# 468332_001_Interface.net
KiCad netlist of a schematic drawn in Altium Designer
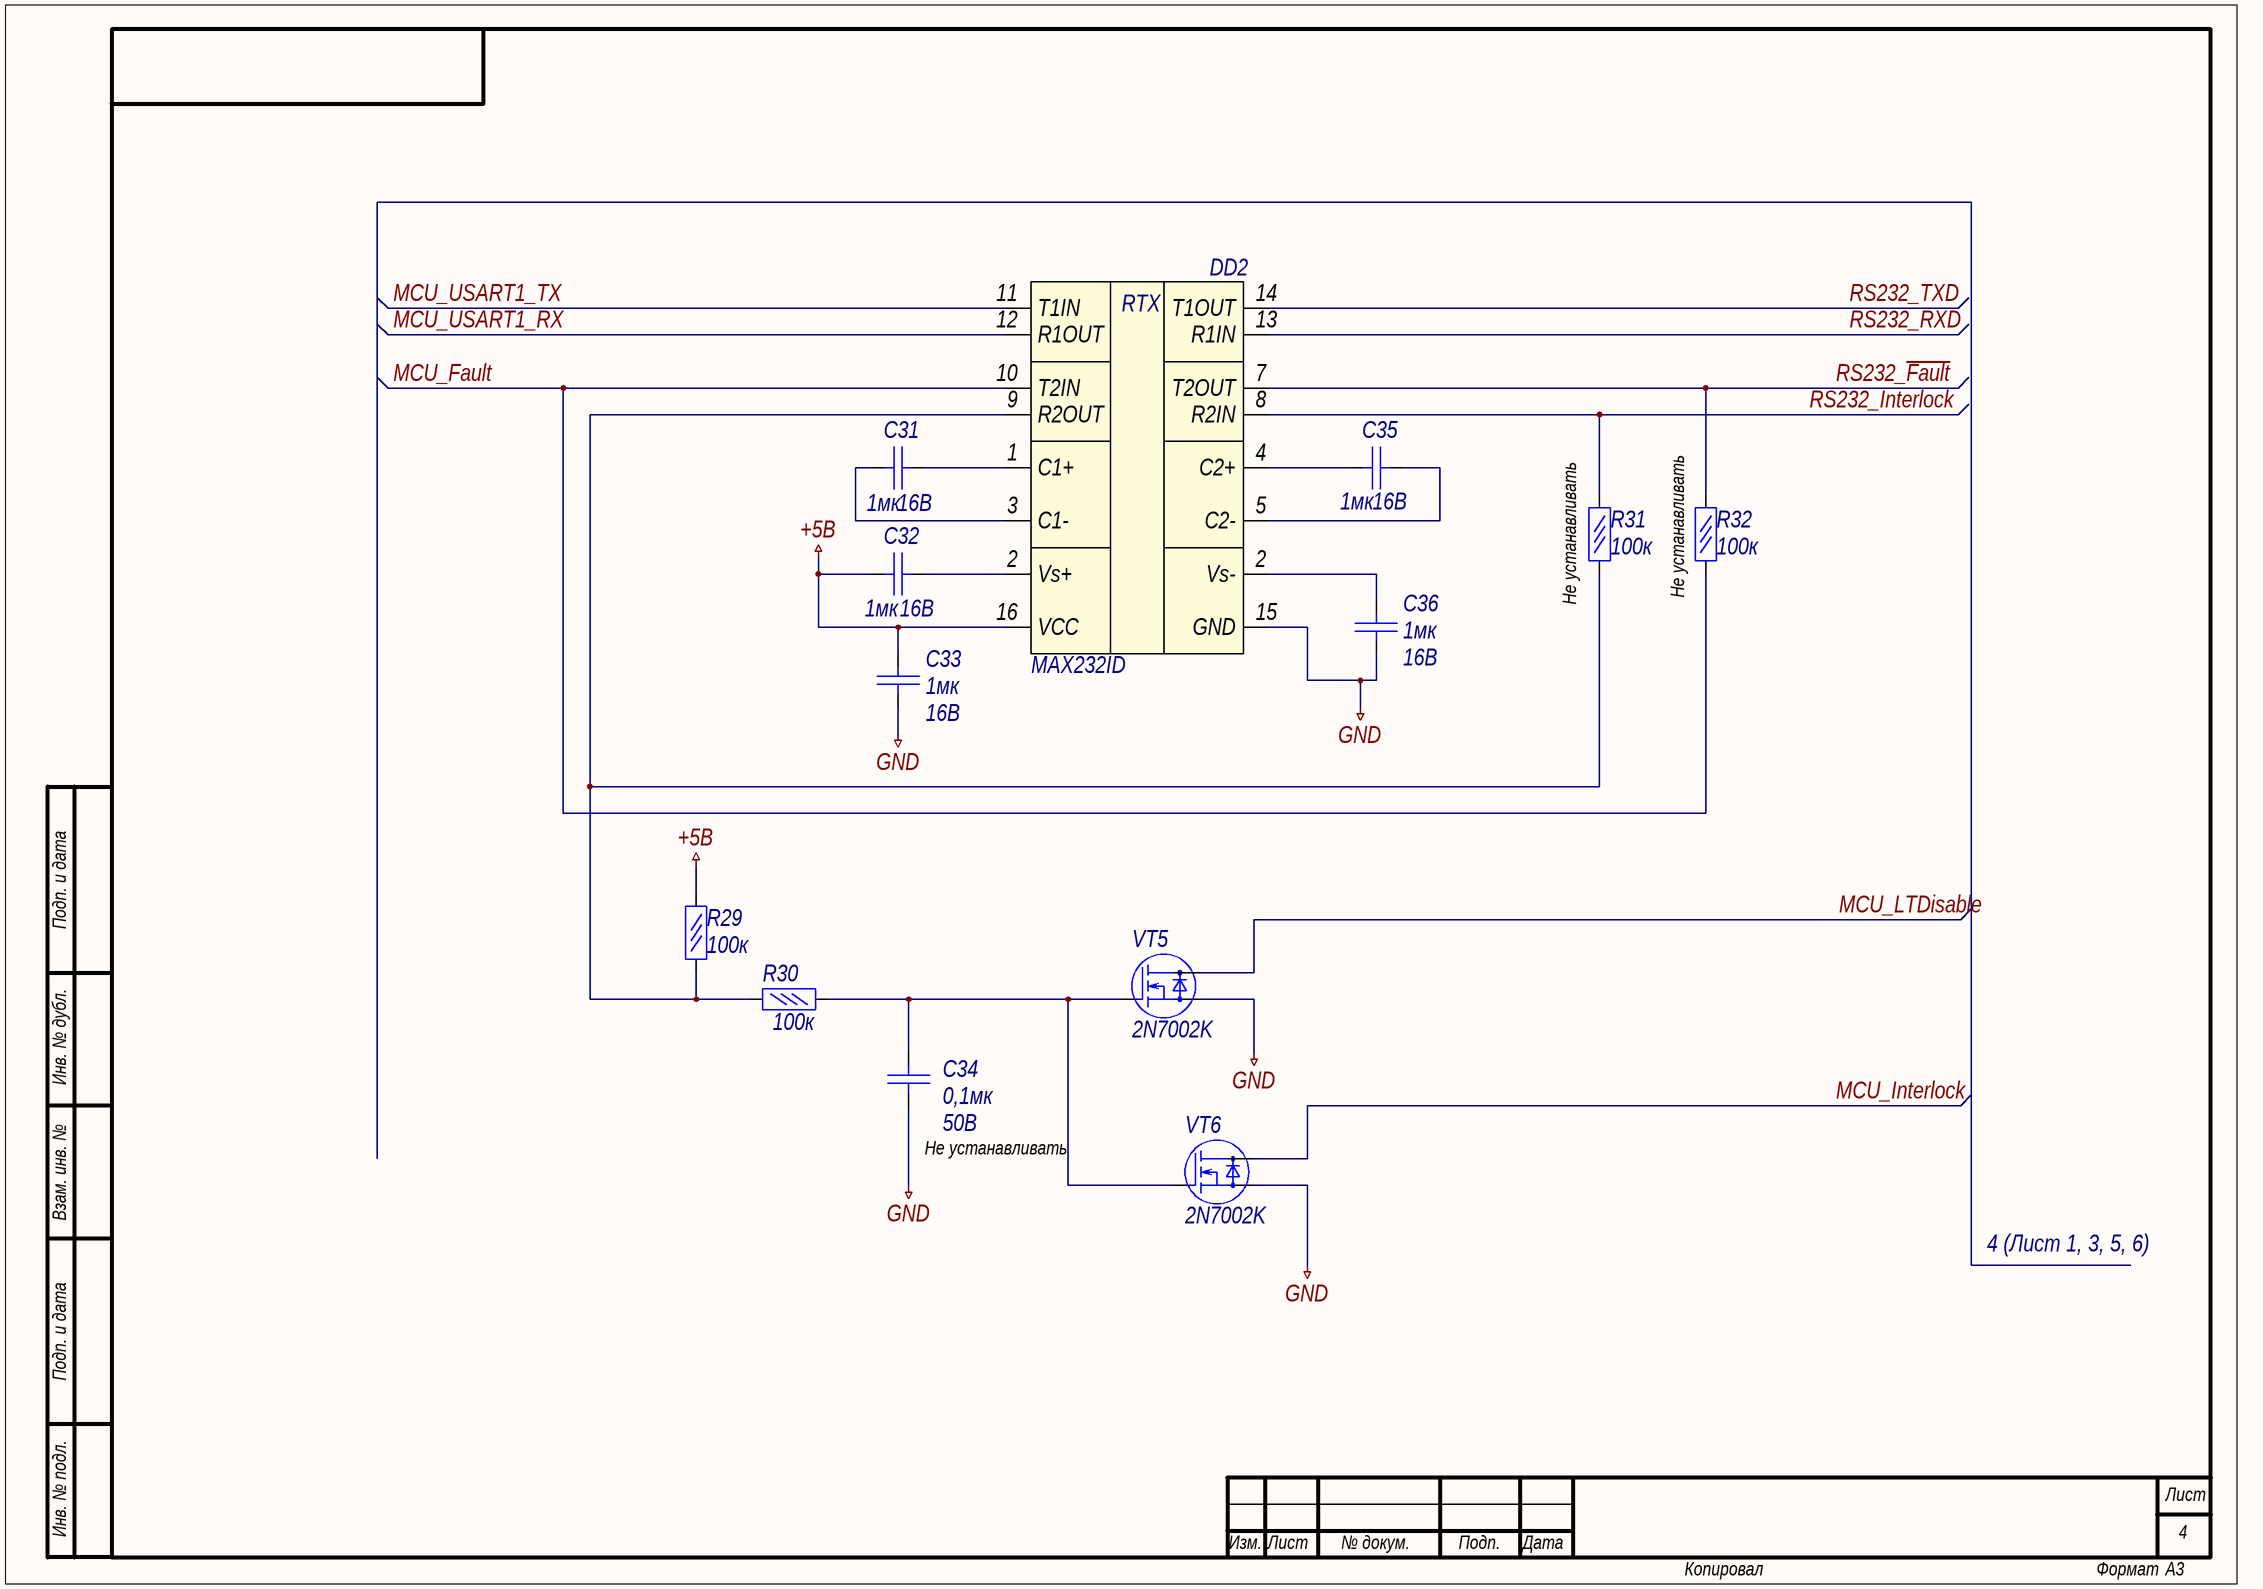
[diagram p0: РЕУН.468332.001_Interface.SchDoc]

(export (version "E")
  (design (tool "Eeschema 10.0.6"))
  (components
    (comp (ref "C31")
      (value "1мк")
      (footprint "C0805_AA")
      (description "Конденсатор кер.")
      (fields (field (name "VOLTAGE") "16В"))
      (libsource (lib "Library_Diana") (part "Конденсатор кер."))
    )
    (comp (ref "C32")
      (value "1мк")
      (footprint "C0805_AA")
      (description "Конденсатор кер.")
      (fields (field (name "VOLTAGE") "16В"))
      (libsource (lib "Library_Diana") (part "Конденсатор кер."))
    )
    (comp (ref "C33")
      (value "1мк")
      (footprint "C0805_AA")
      (description "Конденсатор кер.")
      (fields (field (name "VOLTAGE") "16В"))
      (libsource (lib "Library_Diana") (part "Конденсатор кер."))
    )
    (comp (ref "C34")
      (value "0,1мк")
      (footprint "C0805_AA")
      (description "Конденсатор кер.")
      (fields (field (name "VOLTAGE") "50В"))
      (libsource (lib "Library_Diana") (part "Конденсатор кер."))
    )
    (comp (ref "C35")
      (value "1мк")
      (footprint "C0805_AA")
      (description "Конденсатор кер.")
      (fields (field (name "VOLTAGE") "16В"))
      (libsource (lib "Library_Diana") (part "Конденсатор кер."))
    )
    (comp (ref "C36")
      (value "1мк")
      (footprint "C0805_AA")
      (description "Конденсатор кер.")
      (fields (field (name "VOLTAGE") "16В"))
      (libsource (lib "Library_Diana") (part "Конденсатор кер."))
    )
    (comp (ref "DD2")
      (value "MAX232ID")
      (description "Dual EIA-232 Drivers/Receivers")
      (libsource (lib "Library_Diana") (part "MAX232ID"))
    )
    (comp (ref "R29")
      (value "100к")
      (footprint "R1206")
      (description "Резистор 0,05Вт")
      (libsource (lib "Library_Diana") (part "Резистор  0,05Вт"))
    )
    (comp (ref "R30")
      (value "100к")
      (footprint "R1206")
      (description "Резистор 0,05Вт")
      (libsource (lib "") (part "Резистор  0,05Вт_1"))
    )
    (comp (ref "R31")
      (value "100к")
      (footprint "R1206")
      (description "Резистор 0,05Вт")
      (libsource (lib "Library_Diana") (part "Резистор  0,05Вт"))
    )
    (comp (ref "R32")
      (value "100к")
      (footprint "R1206")
      (description "Резистор 0,05Вт")
      (libsource (lib "Library_Diana") (part "Резистор  0,05Вт"))
    )
    (comp (ref "VT5")
      (value "2N7002K")
      (footprint "SOT:SOT23-3")
      (fields (field (name "NAME") "2N7002K"))
      (libsource (lib "Library_Diana") (part "mosfet-n"))
    )
    (comp (ref "VT6")
      (value "2N7002K")
      (footprint "SOT:SOT23-3")
      (fields (field (name "NAME") "2N7002K"))
      (libsource (lib "Library_Diana") (part "mosfet-n"))
    )
  )
  (nets
    (net (code "1") (name "+5В") (class "Default")
      (node (ref "C32") (pin "2") (pinfunction "2_2") (pintype "passive"))
      (node (ref "C33") (pin "1") (pinfunction "1_1") (pintype "passive"))
      (node (ref "DD2") (pin "16") (pinfunction "VCC_16") (pintype "passive"))
      (node (ref "R29") (pin "1") (pinfunction "1_1") (pintype "passive"))
    )
    (net (code "2") (name "/MCU_Fault") (class "Default")
      (node (ref "DD2") (pin "10") (pinfunction "T2IN_10") (pintype "passive"))
      (node (ref "R32") (pin "2") (pinfunction "2_2") (pintype "passive"))
    )
    (net (code "3") (name "/MCU_Interlock") (class "Default")
      (node (ref "VT6") (pin "3") (pinfunction "D_3") (pintype "passive"))
    )
    (net (code "4") (name "/MCU_LTDisable") (class "Default")
      (node (ref "VT5") (pin "3") (pinfunction "D_3") (pintype "passive"))
    )
    (net (code "5") (name "/MCU_USART1_RX") (class "Default")
      (node (ref "DD2") (pin "12") (pinfunction "R1OUT_12") (pintype "passive"))
    )
    (net (code "6") (name "/MCU_USART1_TX") (class "Default")
      (node (ref "DD2") (pin "11") (pinfunction "T1IN_11") (pintype "passive"))
    )
    (net (code "7") (name "/RS232_Interlock") (class "Default")
      (node (ref "DD2") (pin "8") (pinfunction "R2IN_8") (pintype "passive"))
      (node (ref "R31") (pin "1") (pinfunction "1_1") (pintype "passive"))
    )
    (net (code "8") (name "/RS232_RXD") (class "Default")
      (node (ref "DD2") (pin "13") (pinfunction "R1IN_13") (pintype "passive"))
    )
    (net (code "9") (name "/RS232_TXD") (class "Default")
      (node (ref "DD2") (pin "14") (pinfunction "T1OUT_14") (pintype "passive"))
    )
    (net (code "10") (name "/RS232_~{Fault}") (class "Default")
      (node (ref "DD2") (pin "7") (pinfunction "T2OUT_7") (pintype "passive"))
      (node (ref "R32") (pin "1") (pinfunction "1_1") (pintype "passive"))
    )
    (net (code "11") (name "GND") (class "Default")
      (node (ref "C33") (pin "2") (pinfunction "2_2") (pintype "passive"))
      (node (ref "C34") (pin "1") (pinfunction "1_1") (pintype "passive"))
      (node (ref "C36") (pin "2") (pinfunction "2_2") (pintype "passive"))
      (node (ref "DD2") (pin "15") (pinfunction "GND_15") (pintype "passive"))
      (node (ref "VT5") (pin "2") (pinfunction "S_2") (pintype "passive"))
      (node (ref "VT6") (pin "2") (pinfunction "S_2") (pintype "passive"))
    )
    (net (code "12") (name "Net-(DD2-C1+)") (class "Default")
      (node (ref "C31") (pin "1") (pinfunction "1_1") (pintype "passive"))
      (node (ref "DD2") (pin "1") (pinfunction "C1+_1") (pintype "passive"))
    )
    (net (code "13") (name "Net-(DD2-C1-)") (class "Default")
      (node (ref "C31") (pin "2") (pinfunction "2_2") (pintype "passive"))
      (node (ref "DD2") (pin "3") (pinfunction "C1-_3") (pintype "passive"))
    )
    (net (code "14") (name "Net-(DD2-C2+)") (class "Default")
      (node (ref "C35") (pin "2") (pinfunction "2_2") (pintype "passive"))
      (node (ref "DD2") (pin "4") (pinfunction "C2+_4") (pintype "passive"))
    )
    (net (code "15") (name "Net-(DD2-C2-)") (class "Default")
      (node (ref "C35") (pin "1") (pinfunction "1_1") (pintype "passive"))
      (node (ref "DD2") (pin "5") (pinfunction "C2-_5") (pintype "passive"))
    )
    (net (code "16") (name "Net-(DD2-R2OUT)") (class "Default")
      (node (ref "DD2") (pin "9") (pinfunction "R2OUT_9") (pintype "passive"))
      (node (ref "R29") (pin "2") (pinfunction "2_2") (pintype "passive"))
      (node (ref "R30") (pin "2") (pinfunction "2_2") (pintype "passive"))
      (node (ref "R31") (pin "2") (pinfunction "2_2") (pintype "passive"))
    )
    (net (code "17") (name "Net-(DD2-Vs+)") (class "Default")
      (node (ref "C32") (pin "1") (pinfunction "1_1") (pintype "passive"))
      (node (ref "DD2") (pin "2") (pinfunction "Vs+_2") (pintype "passive"))
    )
    (net (code "18") (name "Net-(DD2-Vs-)") (class "Default")
      (node (ref "C36") (pin "1") (pinfunction "1_1") (pintype "passive"))
      (node (ref "DD2") (pin "2") (pinfunction "Vs-_2") (pintype "passive"))
    )
    (net (code "19") (name "Net-(VT5-G)") (class "Default")
      (node (ref "C34") (pin "2") (pinfunction "2_2") (pintype "passive"))
      (node (ref "R30") (pin "1") (pinfunction "1_1") (pintype "passive"))
      (node (ref "VT5") (pin "1") (pinfunction "G_1") (pintype "passive"))
      (node (ref "VT6") (pin "1") (pinfunction "G_1") (pintype "passive"))
    )
  )
)
